# sklpf.net
KiCad netlist of a schematic drawn in EAGLE
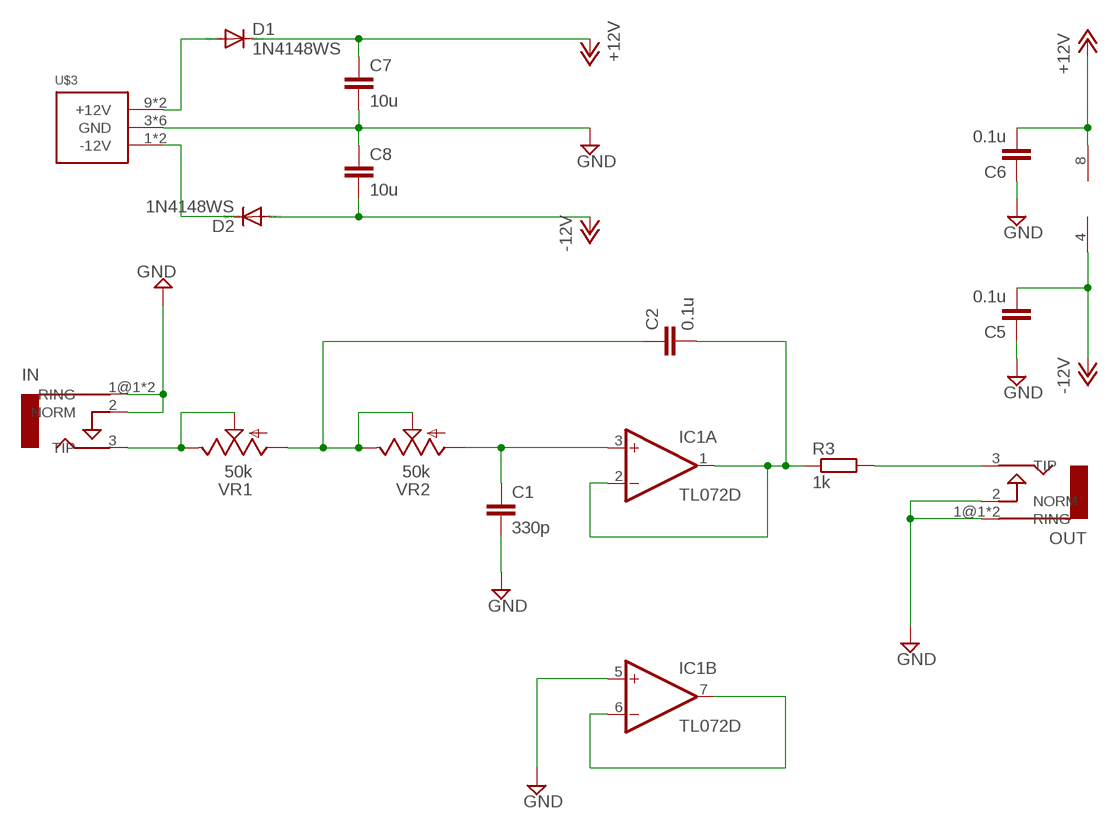
[diagram p0: schematic, sheet 1]

(export (version "E")
  (design (tool "Eeschema 10.0.6"))
  (components
    (comp (ref "C1")
      (value "330p")
      (footprint "eagle-import:C0805")
      (libsource (lib "eagle-import") (part "C-EUC0805"))
    )
    (comp (ref "C2")
      (value "0.1u")
      (footprint "eagle-import:C0805")
      (libsource (lib "eagle-import") (part "C-EUC0805"))
    )
    (comp (ref "C5")
      (value "0.1u")
      (footprint "eagle-import:C0805")
      (libsource (lib "eagle-import") (part "C-EUC0805"))
    )
    (comp (ref "C6")
      (value "0.1u")
      (footprint "eagle-import:C0805")
      (libsource (lib "eagle-import") (part "C-EUC0805"))
    )
    (comp (ref "C7")
      (value "10u")
      (footprint "eagle-import:C0805")
      (libsource (lib "eagle-import") (part "C-EUC0805"))
    )
    (comp (ref "C8")
      (value "10u")
      (footprint "eagle-import:C0805")
      (libsource (lib "eagle-import") (part "C-EUC0805"))
    )
    (comp (ref "D1")
      (value "1N4148WS")
      (footprint "eagle-import:SOD323-W")
      (libsource (lib "eagle-import") (part "DIODE-SOD323-W"))
    )
    (comp (ref "D2")
      (value "1N4148WS")
      (footprint "eagle-import:SOD323-W")
      (libsource (lib "eagle-import") (part "DIODE-SOD323-W"))
    )
    (comp (ref "IC1")
      (value "TL072D")
      (footprint "eagle-import:SO08")
      (libsource (lib "eagle-import") (part "TL072D"))
    )
    (comp (ref "IN")
      (value "AUDIO-JACKERTHENVAR")
      (footprint "eagle-import:ERTHENVAR-JACK")
      (libsource (lib "eagle-import") (part "AUDIO-JACKERTHENVAR"))
    )
    (comp (ref "OUT")
      (value "AUDIO-JACKERTHENVAR")
      (footprint "eagle-import:ERTHENVAR-JACK")
      (libsource (lib "eagle-import") (part "AUDIO-JACKERTHENVAR"))
    )
    (comp (ref "R3")
      (value "1k")
      (footprint "eagle-import:R0805")
      (libsource (lib "eagle-import") (part "R-EU_R0805"))
    )
    (comp (ref "U$3")
      (value "POWER_SIMPLE10")
      (footprint "eagle-import:POWER_10")
      (libsource (lib "eagle-import") (part "POWER_SIMPLE10"))
    )
    (comp (ref "VR1")
      (value "50k")
      (footprint "eagle-import:9MM_SNAP-IN_POT")
      (libsource (lib "eagle-import") (part "9MM_SNAP-IN_POT_"))
    )
    (comp (ref "VR2")
      (value "50k")
      (footprint "eagle-import:9MM_SNAP-IN_POT")
      (libsource (lib "eagle-import") (part "9MM_SNAP-IN_POT_"))
    )
  )
  (nets
    (net (code "1") (name "+12V") (class "Default")
      (node (ref "C6") (pin "2") (pinfunction "2_2") (pintype "passive"))
      (node (ref "C7") (pin "1") (pinfunction "1_1") (pintype "passive"))
      (node (ref "D1") (pin "C") (pinfunction "C_C") (pintype "passive"))
      (node (ref "IC1") (pin "8") (pinfunction "V+_8") (pintype "power_in"))
    )
    (net (code "2") (name "-12V") (class "Default")
      (node (ref "C5") (pin "2") (pinfunction "2_2") (pintype "passive"))
      (node (ref "C8") (pin "2") (pinfunction "2_2") (pintype "passive"))
      (node (ref "D2") (pin "A") (pinfunction "A_A") (pintype "passive"))
      (node (ref "IC1") (pin "4") (pinfunction "V-_4") (pintype "power_in"))
    )
    (net (code "3") (name "GND") (class "Default")
      (node (ref "C1") (pin "2") (pinfunction "2_2") (pintype "passive"))
      (node (ref "C5") (pin "1") (pinfunction "1_1") (pintype "passive"))
      (node (ref "C6") (pin "1") (pinfunction "1_1") (pintype "passive"))
      (node (ref "C7") (pin "2") (pinfunction "2_2") (pintype "passive"))
      (node (ref "C8") (pin "1") (pinfunction "1_1") (pintype "passive"))
      (node (ref "IC1") (pin "5") (pinfunction "+IN_5") (pintype "input"))
      (node (ref "IN") (pin "1@1") (pinfunction "RING_1@1") (pintype "bidirectional"))
      (node (ref "IN") (pin "1@2") (pinfunction "RING_1@2") (pintype "bidirectional"))
      (node (ref "IN") (pin "2") (pinfunction "NORM_2") (pintype "bidirectional"))
      (node (ref "OUT") (pin "1@1") (pinfunction "RING_1@1") (pintype "bidirectional"))
      (node (ref "OUT") (pin "1@2") (pinfunction "RING_1@2") (pintype "bidirectional"))
      (node (ref "OUT") (pin "2") (pinfunction "NORM_2") (pintype "bidirectional"))
      (node (ref "U$3") (pin "3") (pinfunction "GND_3") (pintype "bidirectional"))
      (node (ref "U$3") (pin "4") (pinfunction "GND_4") (pintype "bidirectional"))
      (node (ref "U$3") (pin "5") (pinfunction "GND_5") (pintype "bidirectional"))
      (node (ref "U$3") (pin "6") (pinfunction "GND_6") (pintype "bidirectional"))
      (node (ref "U$3") (pin "7") (pinfunction "GND_7") (pintype "bidirectional"))
      (node (ref "U$3") (pin "8") (pinfunction "GND_8") (pintype "bidirectional"))
    )
    (net (code "4") (name "Net-(D1-PadA)") (class "Default")
      (node (ref "D1") (pin "A") (pinfunction "A_A") (pintype "passive"))
      (node (ref "U$3") (pin "10") (pinfunction "+12V_10") (pintype "bidirectional"))
      (node (ref "U$3") (pin "9") (pinfunction "+12V_9") (pintype "bidirectional"))
    )
    (net (code "5") (name "Net-(D2-PadC)") (class "Default")
      (node (ref "D2") (pin "C") (pinfunction "C_C") (pintype "passive"))
      (node (ref "U$3") (pin "1") (pinfunction "-12V_1") (pintype "bidirectional"))
      (node (ref "U$3") (pin "2") (pinfunction "-12V_2") (pintype "bidirectional"))
    )
    (net (code "6") (name "Net-(IC1A-+IN)") (class "Default")
      (node (ref "C1") (pin "1") (pinfunction "1_1") (pintype "passive"))
      (node (ref "IC1") (pin "3") (pinfunction "+IN_3") (pintype "input"))
      (node (ref "VR2") (pin "1") (pinfunction "A_1") (pintype "passive"))
    )
    (net (code "7") (name "Net-(IC1A--IN)") (class "Default")
      (node (ref "C2") (pin "2") (pinfunction "2_2") (pintype "passive"))
      (node (ref "IC1") (pin "1") (pinfunction "OUT_1") (pintype "output"))
      (node (ref "IC1") (pin "2") (pinfunction "-IN_2") (pintype "input"))
      (node (ref "R3") (pin "1") (pinfunction "1_1") (pintype "passive"))
    )
    (net (code "8") (name "Net-(IC1B--IN)") (class "Default")
      (node (ref "IC1") (pin "6") (pinfunction "-IN_6") (pintype "input"))
      (node (ref "IC1") (pin "7") (pinfunction "OUT_7") (pintype "output"))
    )
    (net (code "9") (name "Net-(IN-TIP)") (class "Default")
      (node (ref "IN") (pin "3") (pinfunction "TIP_3") (pintype "bidirectional"))
      (node (ref "VR1") (pin "2") (pinfunction "S_2") (pintype "passive"))
      (node (ref "VR1") (pin "3") (pinfunction "E_3") (pintype "passive"))
    )
    (net (code "10") (name "Net-(OUT-TIP)") (class "Default")
      (node (ref "OUT") (pin "3") (pinfunction "TIP_3") (pintype "bidirectional"))
      (node (ref "R3") (pin "2") (pinfunction "2_2") (pintype "passive"))
    )
    (net (code "11") (name "Net-(VR1-A)") (class "Default")
      (node (ref "C2") (pin "1") (pinfunction "1_1") (pintype "passive"))
      (node (ref "VR1") (pin "1") (pinfunction "A_1") (pintype "passive"))
      (node (ref "VR2") (pin "2") (pinfunction "S_2") (pintype "passive"))
      (node (ref "VR2") (pin "3") (pinfunction "E_3") (pintype "passive"))
    )
  )
)
